# amp.net
KiCad netlist of a schematic drawn in EAGLE
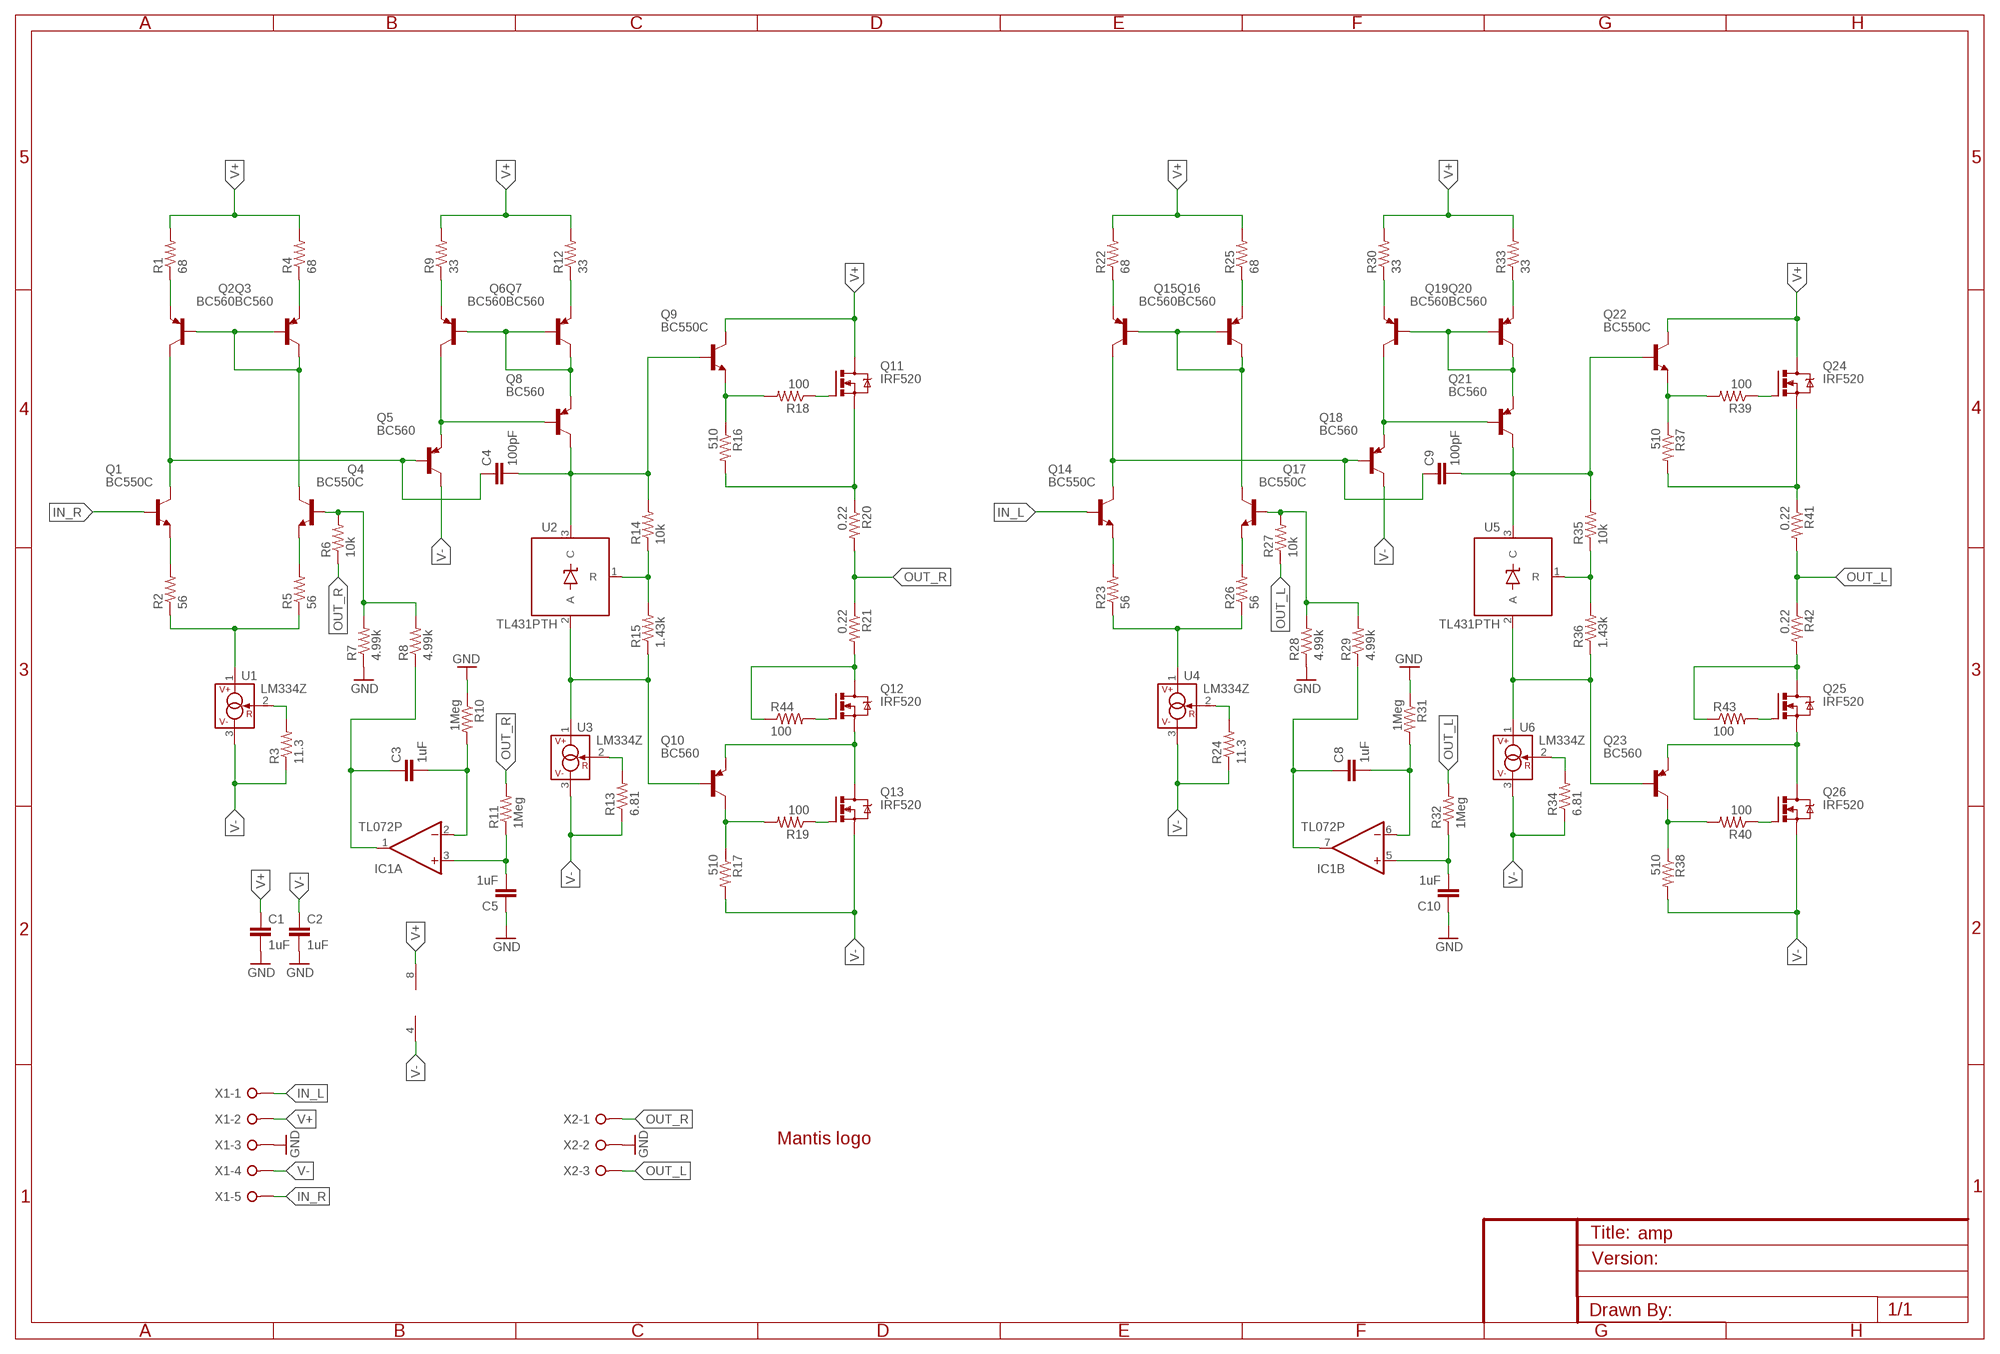
[diagram p0: schematic, sheet 1]

(export (version "E")
  (design (tool "Eeschema 10.0.6"))
  (components
    (comp (ref "C1")
      (value "1uF")
      (footprint "eagle-import:CAP-PTH-SMALL")
      (libsource (lib "eagle-import") (part "CAPPTH"))
    )
    (comp (ref "C2")
      (value "1uF")
      (footprint "eagle-import:CAP-PTH-SMALL")
      (libsource (lib "eagle-import") (part "CAPPTH"))
    )
    (comp (ref "C3")
      (value "1uF")
      (footprint "eagle-import:C5B5.5")
      (libsource (lib "eagle-import") (part "C5/5.5"))
    )
    (comp (ref "C4")
      (value "100pF")
      (footprint "eagle-import:C5B4.5")
      (libsource (lib "eagle-import") (part "C5/4.5"))
    )
    (comp (ref "C5")
      (value "1uF")
      (footprint "eagle-import:C5B5.5")
      (libsource (lib "eagle-import") (part "C5/5.5"))
    )
    (comp (ref "C8")
      (value "1uF")
      (footprint "eagle-import:C5B5.5")
      (libsource (lib "eagle-import") (part "C5/5.5"))
    )
    (comp (ref "C9")
      (value "100pF")
      (footprint "eagle-import:C5B4.5")
      (libsource (lib "eagle-import") (part "C5/4.5"))
    )
    (comp (ref "C10")
      (value "1uF")
      (footprint "eagle-import:C5B5.5")
      (libsource (lib "eagle-import") (part "C5/5.5"))
    )
    (comp (ref "IC1")
      (value "TL072P")
      (footprint "eagle-import:DIL08")
      (libsource (lib "eagle-import") (part "TL072P"))
    )
    (comp (ref "LOGO1")
      (value "LOGO-MANTIS")
      (footprint "eagle-import:LOGO-MANTIS")
      (libsource (lib "eagle-import") (part "LOGO-MANTIS"))
    )
    (comp (ref "Q1")
      (value "BC550C")
      (footprint "eagle-import:TO92-EBC")
      (libsource (lib "eagle-import") (part "BC550C"))
    )
    (comp (ref "Q2")
      (value "BC560")
      (footprint "eagle-import:TO92-EBC")
      (libsource (lib "eagle-import") (part "BC560"))
    )
    (comp (ref "Q3")
      (value "BC560")
      (footprint "eagle-import:TO92-EBC")
      (libsource (lib "eagle-import") (part "BC560"))
    )
    (comp (ref "Q4")
      (value "BC550C")
      (footprint "eagle-import:TO92-EBC")
      (libsource (lib "eagle-import") (part "BC550C"))
    )
    (comp (ref "Q5")
      (value "BC560")
      (footprint "eagle-import:TO92-EBC")
      (libsource (lib "eagle-import") (part "BC560"))
    )
    (comp (ref "Q6")
      (value "BC560")
      (footprint "eagle-import:TO92-EBC")
      (libsource (lib "eagle-import") (part "BC560"))
    )
    (comp (ref "Q7")
      (value "BC560")
      (footprint "eagle-import:TO92-EBC")
      (libsource (lib "eagle-import") (part "BC560"))
    )
    (comp (ref "Q8")
      (value "BC560")
      (footprint "eagle-import:TO92-EBC")
      (libsource (lib "eagle-import") (part "BC560"))
    )
    (comp (ref "Q9")
      (value "BC550C")
      (footprint "eagle-import:TO92-EBC")
      (libsource (lib "eagle-import") (part "BC550C"))
    )
    (comp (ref "Q10")
      (value "BC560")
      (footprint "eagle-import:TO92-EBC")
      (libsource (lib "eagle-import") (part "BC560"))
    )
    (comp (ref "Q11")
      (value "IRF520")
      (footprint "eagle-import:TO220BV")
      (libsource (lib "eagle-import") (part "IRF520"))
    )
    (comp (ref "Q12")
      (value "IRF520")
      (footprint "eagle-import:TO220BV")
      (libsource (lib "eagle-import") (part "IRF520"))
    )
    (comp (ref "Q13")
      (value "IRF520")
      (footprint "eagle-import:TO220BV")
      (libsource (lib "eagle-import") (part "IRF520"))
    )
    (comp (ref "Q14")
      (value "BC550C")
      (footprint "eagle-import:TO92-EBC")
      (libsource (lib "eagle-import") (part "BC550C"))
    )
    (comp (ref "Q15")
      (value "BC560")
      (footprint "eagle-import:TO92-EBC")
      (libsource (lib "eagle-import") (part "BC560"))
    )
    (comp (ref "Q16")
      (value "BC560")
      (footprint "eagle-import:TO92-EBC")
      (libsource (lib "eagle-import") (part "BC560"))
    )
    (comp (ref "Q17")
      (value "BC550C")
      (footprint "eagle-import:TO92-EBC")
      (libsource (lib "eagle-import") (part "BC550C"))
    )
    (comp (ref "Q18")
      (value "BC560")
      (footprint "eagle-import:TO92-EBC")
      (libsource (lib "eagle-import") (part "BC560"))
    )
    (comp (ref "Q19")
      (value "BC560")
      (footprint "eagle-import:TO92-EBC")
      (libsource (lib "eagle-import") (part "BC560"))
    )
    (comp (ref "Q20")
      (value "BC560")
      (footprint "eagle-import:TO92-EBC")
      (libsource (lib "eagle-import") (part "BC560"))
    )
    (comp (ref "Q21")
      (value "BC560")
      (footprint "eagle-import:TO92-EBC")
      (libsource (lib "eagle-import") (part "BC560"))
    )
    (comp (ref "Q22")
      (value "BC550C")
      (footprint "eagle-import:TO92-EBC")
      (libsource (lib "eagle-import") (part "BC550C"))
    )
    (comp (ref "Q23")
      (value "BC560")
      (footprint "eagle-import:TO92-EBC")
      (libsource (lib "eagle-import") (part "BC560"))
    )
    (comp (ref "Q24")
      (value "IRF520")
      (footprint "eagle-import:TO220BV")
      (libsource (lib "eagle-import") (part "IRF520"))
    )
    (comp (ref "Q25")
      (value "IRF520")
      (footprint "eagle-import:TO220BV")
      (libsource (lib "eagle-import") (part "IRF520"))
    )
    (comp (ref "Q26")
      (value "IRF520")
      (footprint "eagle-import:TO220BV")
      (libsource (lib "eagle-import") (part "IRF520"))
    )
    (comp (ref "R1")
      (value "68")
      (footprint "eagle-import:AXIAL-0.4")
      (libsource (lib "eagle-import") (part "RESISTORPTH-1/4W"))
    )
    (comp (ref "R2")
      (value "56")
      (footprint "eagle-import:AXIAL-0.4")
      (libsource (lib "eagle-import") (part "RESISTORPTH-1/4W"))
    )
    (comp (ref "R3")
      (value "11.3")
      (footprint "eagle-import:AXIAL-0.4")
      (libsource (lib "eagle-import") (part "RESISTORPTH-1/4W"))
    )
    (comp (ref "R4")
      (value "68")
      (footprint "eagle-import:AXIAL-0.4")
      (libsource (lib "eagle-import") (part "RESISTORPTH-1/4W"))
    )
    (comp (ref "R5")
      (value "56")
      (footprint "eagle-import:AXIAL-0.4")
      (libsource (lib "eagle-import") (part "RESISTORPTH-1/4W"))
    )
    (comp (ref "R6")
      (value "10k")
      (footprint "eagle-import:AXIAL-0.4")
      (libsource (lib "eagle-import") (part "RESISTORPTH-1/4W"))
    )
    (comp (ref "R7")
      (value "4.99k")
      (footprint "eagle-import:AXIAL-0.4")
      (libsource (lib "eagle-import") (part "RESISTORPTH-1/4W"))
    )
    (comp (ref "R8")
      (value "4.99k")
      (footprint "eagle-import:AXIAL-0.4")
      (libsource (lib "eagle-import") (part "RESISTORPTH-1/4W"))
    )
    (comp (ref "R9")
      (value "33")
      (footprint "eagle-import:AXIAL-0.4")
      (libsource (lib "eagle-import") (part "RESISTORPTH-1/4W"))
    )
    (comp (ref "R10")
      (value "1Meg")
      (footprint "eagle-import:AXIAL-0.4")
      (libsource (lib "eagle-import") (part "RESISTORPTH-1/4W"))
    )
    (comp (ref "R11")
      (value "1Meg")
      (footprint "eagle-import:AXIAL-0.4")
      (libsource (lib "eagle-import") (part "RESISTORPTH-1/4W"))
    )
    (comp (ref "R12")
      (value "33")
      (footprint "eagle-import:AXIAL-0.4")
      (libsource (lib "eagle-import") (part "RESISTORPTH-1/4W"))
    )
    (comp (ref "R13")
      (value "6.81")
      (footprint "eagle-import:AXIAL-0.4")
      (libsource (lib "eagle-import") (part "RESISTORPTH-1/4W"))
    )
    (comp (ref "R14")
      (value "10k")
      (footprint "eagle-import:AXIAL-0.4")
      (libsource (lib "eagle-import") (part "RESISTORPTH-1/4W"))
    )
    (comp (ref "R15")
      (value "1.43k")
      (footprint "eagle-import:AXIAL-0.4")
      (libsource (lib "eagle-import") (part "RESISTORPTH-1/4W"))
    )
    (comp (ref "R16")
      (value "510")
      (footprint "eagle-import:AXIAL-0.4")
      (libsource (lib "eagle-import") (part "RESISTORPTH-1/4W"))
    )
    (comp (ref "R17")
      (value "510")
      (footprint "eagle-import:AXIAL-0.4")
      (libsource (lib "eagle-import") (part "RESISTORPTH-1/4W"))
    )
    (comp (ref "R18")
      (value "100")
      (footprint "eagle-import:AXIAL-0.4")
      (libsource (lib "eagle-import") (part "RESISTORPTH-1/4W"))
    )
    (comp (ref "R19")
      (value "100")
      (footprint "eagle-import:AXIAL-0.4")
      (libsource (lib "eagle-import") (part "RESISTORPTH-1/4W"))
    )
    (comp (ref "R20")
      (value "0.22")
      (footprint "eagle-import:AXIAL-0.4")
      (libsource (lib "eagle-import") (part "RESISTORPTH-1/4W"))
    )
    (comp (ref "R21")
      (value "0.22")
      (footprint "eagle-import:AXIAL-0.4")
      (libsource (lib "eagle-import") (part "RESISTORPTH-1/4W"))
    )
    (comp (ref "R22")
      (value "68")
      (footprint "eagle-import:AXIAL-0.4")
      (libsource (lib "eagle-import") (part "RESISTORPTH-1/4W"))
    )
    (comp (ref "R23")
      (value "56")
      (footprint "eagle-import:AXIAL-0.4")
      (libsource (lib "eagle-import") (part "RESISTORPTH-1/4W"))
    )
    (comp (ref "R24")
      (value "11.3")
      (footprint "eagle-import:AXIAL-0.4")
      (libsource (lib "eagle-import") (part "RESISTORPTH-1/4W"))
    )
    (comp (ref "R25")
      (value "68")
      (footprint "eagle-import:AXIAL-0.4")
      (libsource (lib "eagle-import") (part "RESISTORPTH-1/4W"))
    )
    (comp (ref "R26")
      (value "56")
      (footprint "eagle-import:AXIAL-0.4")
      (libsource (lib "eagle-import") (part "RESISTORPTH-1/4W"))
    )
    (comp (ref "R27")
      (value "10k")
      (footprint "eagle-import:AXIAL-0.4")
      (libsource (lib "eagle-import") (part "RESISTORPTH-1/4W"))
    )
    (comp (ref "R28")
      (value "4.99k")
      (footprint "eagle-import:AXIAL-0.4")
      (libsource (lib "eagle-import") (part "RESISTORPTH-1/4W"))
    )
    (comp (ref "R29")
      (value "4.99k")
      (footprint "eagle-import:AXIAL-0.4")
      (libsource (lib "eagle-import") (part "RESISTORPTH-1/4W"))
    )
    (comp (ref "R30")
      (value "33")
      (footprint "eagle-import:AXIAL-0.4")
      (libsource (lib "eagle-import") (part "RESISTORPTH-1/4W"))
    )
    (comp (ref "R31")
      (value "1Meg")
      (footprint "eagle-import:AXIAL-0.4")
      (libsource (lib "eagle-import") (part "RESISTORPTH-1/4W"))
    )
    (comp (ref "R32")
      (value "1Meg")
      (footprint "eagle-import:AXIAL-0.4")
      (libsource (lib "eagle-import") (part "RESISTORPTH-1/4W"))
    )
    (comp (ref "R33")
      (value "33")
      (footprint "eagle-import:AXIAL-0.4")
      (libsource (lib "eagle-import") (part "RESISTORPTH-1/4W"))
    )
    (comp (ref "R34")
      (value "6.81")
      (footprint "eagle-import:AXIAL-0.4")
      (libsource (lib "eagle-import") (part "RESISTORPTH-1/4W"))
    )
    (comp (ref "R35")
      (value "10k")
      (footprint "eagle-import:AXIAL-0.4")
      (libsource (lib "eagle-import") (part "RESISTORPTH-1/4W"))
    )
    (comp (ref "R36")
      (value "1.43k")
      (footprint "eagle-import:AXIAL-0.4")
      (libsource (lib "eagle-import") (part "RESISTORPTH-1/4W"))
    )
    (comp (ref "R37")
      (value "510")
      (footprint "eagle-import:AXIAL-0.4")
      (libsource (lib "eagle-import") (part "RESISTORPTH-1/4W"))
    )
    (comp (ref "R38")
      (value "510")
      (footprint "eagle-import:AXIAL-0.4")
      (libsource (lib "eagle-import") (part "RESISTORPTH-1/4W"))
    )
    (comp (ref "R39")
      (value "100")
      (footprint "eagle-import:AXIAL-0.4")
      (libsource (lib "eagle-import") (part "RESISTORPTH-1/4W"))
    )
    (comp (ref "R40")
      (value "100")
      (footprint "eagle-import:AXIAL-0.4")
      (libsource (lib "eagle-import") (part "RESISTORPTH-1/4W"))
    )
    (comp (ref "R41")
      (value "0.22")
      (footprint "eagle-import:AXIAL-0.4")
      (libsource (lib "eagle-import") (part "RESISTORPTH-1/4W"))
    )
    (comp (ref "R42")
      (value "0.22")
      (footprint "eagle-import:AXIAL-0.4")
      (libsource (lib "eagle-import") (part "RESISTORPTH-1/4W"))
    )
    (comp (ref "R43")
      (value "100")
      (footprint "eagle-import:AXIAL-0.4")
      (libsource (lib "eagle-import") (part "RESISTORPTH-1/4W"))
    )
    (comp (ref "R44")
      (value "100")
      (footprint "eagle-import:AXIAL-0.4")
      (libsource (lib "eagle-import") (part "RESISTORPTH-1/4W"))
    )
    (comp (ref "U1")
      (value "LM334Z")
      (footprint "eagle-import:TO-92")
      (libsource (lib "eagle-import") (part "LM334Z"))
    )
    (comp (ref "U2")
      (value "TL431PTH")
      (footprint "eagle-import:TO-92")
      (libsource (lib "eagle-import") (part "TL431PTH"))
    )
    (comp (ref "U3")
      (value "LM334Z")
      (footprint "eagle-import:TO-92")
      (libsource (lib "eagle-import") (part "LM334Z"))
    )
    (comp (ref "U4")
      (value "LM334Z")
      (footprint "eagle-import:TO-92")
      (libsource (lib "eagle-import") (part "LM334Z"))
    )
    (comp (ref "U5")
      (value "TL431PTH")
      (footprint "eagle-import:TO-92")
      (libsource (lib "eagle-import") (part "TL431PTH"))
    )
    (comp (ref "U6")
      (value "LM334Z")
      (footprint "eagle-import:TO-92")
      (libsource (lib "eagle-import") (part "LM334Z"))
    )
    (comp (ref "X1")
      (value "W237-05P")
      (footprint "eagle-import:W237-5P")
      (libsource (lib "eagle-import") (part "W237-05P"))
    )
    (comp (ref "X2")
      (value "W237-3E")
      (footprint "eagle-import:W237-3E")
      (libsource (lib "eagle-import") (part "W237-3E"))
    )
  )
  (nets
    (net (code "1") (name "GND") (class "Default")
      (node (ref "C1") (pin "2") (pinfunction "2_2") (pintype "passive"))
      (node (ref "C10") (pin "1") (pinfunction "1_1") (pintype "passive"))
      (node (ref "C2") (pin "2") (pinfunction "2_2") (pintype "passive"))
      (node (ref "C5") (pin "1") (pinfunction "1_1") (pintype "passive"))
      (node (ref "R10") (pin "P$1") (pinfunction "1_P$1") (pintype "passive"))
      (node (ref "R28") (pin "P$1") (pinfunction "1_P$1") (pintype "passive"))
      (node (ref "R31") (pin "P$1") (pinfunction "1_P$1") (pintype "passive"))
      (node (ref "R7") (pin "P$1") (pinfunction "1_P$1") (pintype "passive"))
      (node (ref "X1") (pin "3") (pinfunction "KL_3") (pintype "passive"))
      (node (ref "X2") (pin "2") (pinfunction "KL_2") (pintype "passive"))
    )
    (net (code "2") (name "IN_L") (class "Default")
      (node (ref "Q14") (pin "B") (pinfunction "B_B") (pintype "passive"))
      (node (ref "X1") (pin "1") (pinfunction "KL_1") (pintype "passive"))
    )
    (net (code "3") (name "IN_R") (class "Default")
      (node (ref "Q1") (pin "B") (pinfunction "B_B") (pintype "passive"))
      (node (ref "X1") (pin "5") (pinfunction "KL_5") (pintype "passive"))
    )
    (net (code "4") (name "Net-(C4-Pad1)") (class "Default")
      (node (ref "C4") (pin "1") (pinfunction "1_1") (pintype "passive"))
      (node (ref "Q1") (pin "C") (pinfunction "C_C") (pintype "passive"))
      (node (ref "Q2") (pin "C") (pinfunction "C_C") (pintype "passive"))
      (node (ref "Q5") (pin "B") (pinfunction "B_B") (pintype "passive"))
    )
    (net (code "5") (name "Net-(C9-Pad1)") (class "Default")
      (node (ref "C9") (pin "1") (pinfunction "1_1") (pintype "passive"))
      (node (ref "Q14") (pin "C") (pinfunction "C_C") (pintype "passive"))
      (node (ref "Q15") (pin "C") (pinfunction "C_C") (pintype "passive"))
      (node (ref "Q18") (pin "B") (pinfunction "B_B") (pintype "passive"))
    )
    (net (code "6") (name "Net-(IC1A-+IN)") (class "Default")
      (node (ref "C5") (pin "2") (pinfunction "2_2") (pintype "passive"))
      (node (ref "IC1") (pin "3") (pinfunction "+IN_3") (pintype "input"))
      (node (ref "R11") (pin "P$1") (pinfunction "1_P$1") (pintype "passive"))
    )
    (net (code "7") (name "Net-(IC1A--IN)") (class "Default")
      (node (ref "C3") (pin "2") (pinfunction "2_2") (pintype "passive"))
      (node (ref "IC1") (pin "2") (pinfunction "-IN_2") (pintype "input"))
      (node (ref "R10") (pin "P$2") (pinfunction "2_P$2") (pintype "passive"))
    )
    (net (code "8") (name "Net-(IC1A-OUT)") (class "Default")
      (node (ref "C3") (pin "1") (pinfunction "1_1") (pintype "passive"))
      (node (ref "IC1") (pin "1") (pinfunction "OUT_1") (pintype "output"))
      (node (ref "R8") (pin "P$1") (pinfunction "1_P$1") (pintype "passive"))
    )
    (net (code "9") (name "Net-(IC1B-+IN)") (class "Default")
      (node (ref "C10") (pin "2") (pinfunction "2_2") (pintype "passive"))
      (node (ref "IC1") (pin "5") (pinfunction "+IN_5") (pintype "input"))
      (node (ref "R32") (pin "P$1") (pinfunction "1_P$1") (pintype "passive"))
    )
    (net (code "10") (name "Net-(IC1B--IN)") (class "Default")
      (node (ref "C8") (pin "2") (pinfunction "2_2") (pintype "passive"))
      (node (ref "IC1") (pin "6") (pinfunction "-IN_6") (pintype "input"))
      (node (ref "R31") (pin "P$2") (pinfunction "2_P$2") (pintype "passive"))
    )
    (net (code "11") (name "Net-(IC1B-OUT)") (class "Default")
      (node (ref "C8") (pin "1") (pinfunction "1_1") (pintype "passive"))
      (node (ref "IC1") (pin "7") (pinfunction "OUT_7") (pintype "output"))
      (node (ref "R29") (pin "P$1") (pinfunction "1_P$1") (pintype "passive"))
    )
    (net (code "12") (name "Net-(Q2-PadB)") (class "Default")
      (node (ref "Q2") (pin "B") (pinfunction "B_B") (pintype "passive"))
      (node (ref "Q3") (pin "B") (pinfunction "B_B") (pintype "passive"))
      (node (ref "Q3") (pin "C") (pinfunction "C_C") (pintype "passive"))
      (node (ref "Q4") (pin "C") (pinfunction "C_C") (pintype "passive"))
    )
    (net (code "13") (name "Net-(Q5-PadE)") (class "Default")
      (node (ref "Q5") (pin "E") (pinfunction "E_E") (pintype "passive"))
      (node (ref "Q6") (pin "C") (pinfunction "C_C") (pintype "passive"))
      (node (ref "Q8") (pin "B") (pinfunction "B_B") (pintype "passive"))
    )
    (net (code "14") (name "Net-(Q6-PadB)") (class "Default")
      (node (ref "Q6") (pin "B") (pinfunction "B_B") (pintype "passive"))
      (node (ref "Q7") (pin "B") (pinfunction "B_B") (pintype "passive"))
      (node (ref "Q7") (pin "C") (pinfunction "C_C") (pintype "passive"))
      (node (ref "Q8") (pin "E") (pinfunction "E_E") (pintype "passive"))
    )
    (net (code "15") (name "Net-(Q10-PadE)") (class "Default")
      (node (ref "Q10") (pin "E") (pinfunction "E_E") (pintype "passive"))
      (node (ref "Q12") (pin "S") (pinfunction "S_S") (pintype "passive"))
      (node (ref "Q13") (pin "D") (pinfunction "D_D") (pintype "passive"))
    )
    (net (code "16") (name "Net-(Q15-PadB)") (class "Default")
      (node (ref "Q15") (pin "B") (pinfunction "B_B") (pintype "passive"))
      (node (ref "Q16") (pin "B") (pinfunction "B_B") (pintype "passive"))
      (node (ref "Q16") (pin "C") (pinfunction "C_C") (pintype "passive"))
      (node (ref "Q17") (pin "C") (pinfunction "C_C") (pintype "passive"))
    )
    (net (code "17") (name "Net-(Q18-PadE)") (class "Default")
      (node (ref "Q18") (pin "E") (pinfunction "E_E") (pintype "passive"))
      (node (ref "Q19") (pin "C") (pinfunction "C_C") (pintype "passive"))
      (node (ref "Q21") (pin "B") (pinfunction "B_B") (pintype "passive"))
    )
    (net (code "18") (name "Net-(Q19-PadB)") (class "Default")
      (node (ref "Q19") (pin "B") (pinfunction "B_B") (pintype "passive"))
      (node (ref "Q20") (pin "B") (pinfunction "B_B") (pintype "passive"))
      (node (ref "Q20") (pin "C") (pinfunction "C_C") (pintype "passive"))
      (node (ref "Q21") (pin "E") (pinfunction "E_E") (pintype "passive"))
    )
    (net (code "19") (name "Net-(Q23-PadE)") (class "Default")
      (node (ref "Q23") (pin "E") (pinfunction "E_E") (pintype "passive"))
      (node (ref "Q25") (pin "S") (pinfunction "S_S") (pintype "passive"))
      (node (ref "Q26") (pin "D") (pinfunction "D_D") (pintype "passive"))
    )
    (net (code "20") (name "Net-(R1-1)") (class "Default")
      (node (ref "Q2") (pin "E") (pinfunction "E_E") (pintype "passive"))
      (node (ref "R1") (pin "P$1") (pinfunction "1_P$1") (pintype "passive"))
    )
    (net (code "21") (name "Net-(R2-1)") (class "Default")
      (node (ref "R2") (pin "P$1") (pinfunction "1_P$1") (pintype "passive"))
      (node (ref "R5") (pin "P$1") (pinfunction "1_P$1") (pintype "passive"))
      (node (ref "U1") (pin "1") (pinfunction "V+_1") (pintype "passive"))
    )
    (net (code "22") (name "Net-(R2-2)") (class "Default")
      (node (ref "Q1") (pin "E") (pinfunction "E_E") (pintype "passive"))
      (node (ref "R2") (pin "P$2") (pinfunction "2_P$2") (pintype "passive"))
    )
    (net (code "23") (name "Net-(R3-2)") (class "Default")
      (node (ref "R3") (pin "P$2") (pinfunction "2_P$2") (pintype "passive"))
      (node (ref "U1") (pin "2") (pinfunction "R_2") (pintype "passive"))
    )
    (net (code "24") (name "Net-(R4-1)") (class "Default")
      (node (ref "Q3") (pin "E") (pinfunction "E_E") (pintype "passive"))
      (node (ref "R4") (pin "P$1") (pinfunction "1_P$1") (pintype "passive"))
    )
    (net (code "25") (name "Net-(R5-2)") (class "Default")
      (node (ref "Q4") (pin "E") (pinfunction "E_E") (pintype "passive"))
      (node (ref "R5") (pin "P$2") (pinfunction "2_P$2") (pintype "passive"))
    )
    (net (code "26") (name "Net-(R6-2)") (class "Default")
      (node (ref "Q4") (pin "B") (pinfunction "B_B") (pintype "passive"))
      (node (ref "R6") (pin "P$2") (pinfunction "2_P$2") (pintype "passive"))
      (node (ref "R7") (pin "P$2") (pinfunction "2_P$2") (pintype "passive"))
      (node (ref "R8") (pin "P$2") (pinfunction "2_P$2") (pintype "passive"))
    )
    (net (code "27") (name "Net-(R9-1)") (class "Default")
      (node (ref "Q6") (pin "E") (pinfunction "E_E") (pintype "passive"))
      (node (ref "R9") (pin "P$1") (pinfunction "1_P$1") (pintype "passive"))
    )
    (net (code "28") (name "Net-(R12-1)") (class "Default")
      (node (ref "Q7") (pin "E") (pinfunction "E_E") (pintype "passive"))
      (node (ref "R12") (pin "P$1") (pinfunction "1_P$1") (pintype "passive"))
    )
    (net (code "29") (name "Net-(R13-2)") (class "Default")
      (node (ref "R13") (pin "P$2") (pinfunction "2_P$2") (pintype "passive"))
      (node (ref "U3") (pin "2") (pinfunction "R_2") (pintype "passive"))
    )
    (net (code "30") (name "Net-(R14-1)") (class "Default")
      (node (ref "R14") (pin "P$1") (pinfunction "1_P$1") (pintype "passive"))
      (node (ref "R15") (pin "P$2") (pinfunction "2_P$2") (pintype "passive"))
      (node (ref "U2") (pin "1") (pinfunction "R_1") (pintype "bidirectional"))
    )
    (net (code "31") (name "Net-(R14-2)") (class "Default")
      (node (ref "C4") (pin "2") (pinfunction "2_2") (pintype "passive"))
      (node (ref "Q8") (pin "C") (pinfunction "C_C") (pintype "passive"))
      (node (ref "Q9") (pin "B") (pinfunction "B_B") (pintype "passive"))
      (node (ref "R14") (pin "P$2") (pinfunction "2_P$2") (pintype "passive"))
      (node (ref "U2") (pin "3") (pinfunction "C_3") (pintype "bidirectional"))
    )
    (net (code "32") (name "Net-(R15-1)") (class "Default")
      (node (ref "Q10") (pin "B") (pinfunction "B_B") (pintype "passive"))
      (node (ref "R15") (pin "P$1") (pinfunction "1_P$1") (pintype "passive"))
      (node (ref "U2") (pin "2") (pinfunction "A_2") (pintype "bidirectional"))
      (node (ref "U3") (pin "1") (pinfunction "V+_1") (pintype "passive"))
    )
    (net (code "33") (name "Net-(R16-1)") (class "Default")
      (node (ref "Q9") (pin "E") (pinfunction "E_E") (pintype "passive"))
      (node (ref "R16") (pin "P$1") (pinfunction "1_P$1") (pintype "passive"))
      (node (ref "R18") (pin "P$2") (pinfunction "2_P$2") (pintype "passive"))
    )
    (net (code "34") (name "Net-(R16-2)") (class "Default")
      (node (ref "Q11") (pin "S") (pinfunction "S_S") (pintype "passive"))
      (node (ref "R16") (pin "P$2") (pinfunction "2_P$2") (pintype "passive"))
      (node (ref "R20") (pin "P$1") (pinfunction "1_P$1") (pintype "passive"))
    )
    (net (code "35") (name "Net-(R17-1)") (class "Default")
      (node (ref "Q10") (pin "C") (pinfunction "C_C") (pintype "passive"))
      (node (ref "R17") (pin "P$1") (pinfunction "1_P$1") (pintype "passive"))
      (node (ref "R19") (pin "P$2") (pinfunction "2_P$2") (pintype "passive"))
    )
    (net (code "36") (name "Net-(R18-1)") (class "Default")
      (node (ref "Q11") (pin "G") (pinfunction "G_G") (pintype "passive"))
      (node (ref "R18") (pin "P$1") (pinfunction "1_P$1") (pintype "passive"))
    )
    (net (code "37") (name "Net-(R19-1)") (class "Default")
      (node (ref "Q13") (pin "G") (pinfunction "G_G") (pintype "passive"))
      (node (ref "R19") (pin "P$1") (pinfunction "1_P$1") (pintype "passive"))
    )
    (net (code "38") (name "Net-(R21-2)") (class "Default")
      (node (ref "Q12") (pin "D") (pinfunction "D_D") (pintype "passive"))
      (node (ref "R21") (pin "P$2") (pinfunction "2_P$2") (pintype "passive"))
      (node (ref "R44") (pin "P$1") (pinfunction "1_P$1") (pintype "passive"))
    )
    (net (code "39") (name "Net-(R22-1)") (class "Default")
      (node (ref "Q15") (pin "E") (pinfunction "E_E") (pintype "passive"))
      (node (ref "R22") (pin "P$1") (pinfunction "1_P$1") (pintype "passive"))
    )
    (net (code "40") (name "Net-(R23-1)") (class "Default")
      (node (ref "R23") (pin "P$1") (pinfunction "1_P$1") (pintype "passive"))
      (node (ref "R26") (pin "P$1") (pinfunction "1_P$1") (pintype "passive"))
      (node (ref "U4") (pin "1") (pinfunction "V+_1") (pintype "passive"))
    )
    (net (code "41") (name "Net-(R23-2)") (class "Default")
      (node (ref "Q14") (pin "E") (pinfunction "E_E") (pintype "passive"))
      (node (ref "R23") (pin "P$2") (pinfunction "2_P$2") (pintype "passive"))
    )
    (net (code "42") (name "Net-(R24-2)") (class "Default")
      (node (ref "R24") (pin "P$2") (pinfunction "2_P$2") (pintype "passive"))
      (node (ref "U4") (pin "2") (pinfunction "R_2") (pintype "passive"))
    )
    (net (code "43") (name "Net-(R25-1)") (class "Default")
      (node (ref "Q16") (pin "E") (pinfunction "E_E") (pintype "passive"))
      (node (ref "R25") (pin "P$1") (pinfunction "1_P$1") (pintype "passive"))
    )
    (net (code "44") (name "Net-(R26-2)") (class "Default")
      (node (ref "Q17") (pin "E") (pinfunction "E_E") (pintype "passive"))
      (node (ref "R26") (pin "P$2") (pinfunction "2_P$2") (pintype "passive"))
    )
    (net (code "45") (name "Net-(R27-2)") (class "Default")
      (node (ref "Q17") (pin "B") (pinfunction "B_B") (pintype "passive"))
      (node (ref "R27") (pin "P$2") (pinfunction "2_P$2") (pintype "passive"))
      (node (ref "R28") (pin "P$2") (pinfunction "2_P$2") (pintype "passive"))
      (node (ref "R29") (pin "P$2") (pinfunction "2_P$2") (pintype "passive"))
    )
    (net (code "46") (name "Net-(R30-1)") (class "Default")
      (node (ref "Q19") (pin "E") (pinfunction "E_E") (pintype "passive"))
      (node (ref "R30") (pin "P$1") (pinfunction "1_P$1") (pintype "passive"))
    )
    (net (code "47") (name "Net-(R33-1)") (class "Default")
      (node (ref "Q20") (pin "E") (pinfunction "E_E") (pintype "passive"))
      (node (ref "R33") (pin "P$1") (pinfunction "1_P$1") (pintype "passive"))
    )
    (net (code "48") (name "Net-(R34-2)") (class "Default")
      (node (ref "R34") (pin "P$2") (pinfunction "2_P$2") (pintype "passive"))
      (node (ref "U6") (pin "2") (pinfunction "R_2") (pintype "passive"))
    )
    (net (code "49") (name "Net-(R35-1)") (class "Default")
      (node (ref "R35") (pin "P$1") (pinfunction "1_P$1") (pintype "passive"))
      (node (ref "R36") (pin "P$2") (pinfunction "2_P$2") (pintype "passive"))
      (node (ref "U5") (pin "1") (pinfunction "R_1") (pintype "bidirectional"))
    )
    (net (code "50") (name "Net-(R35-2)") (class "Default")
      (node (ref "C9") (pin "2") (pinfunction "2_2") (pintype "passive"))
      (node (ref "Q21") (pin "C") (pinfunction "C_C") (pintype "passive"))
      (node (ref "Q22") (pin "B") (pinfunction "B_B") (pintype "passive"))
      (node (ref "R35") (pin "P$2") (pinfunction "2_P$2") (pintype "passive"))
      (node (ref "U5") (pin "3") (pinfunction "C_3") (pintype "bidirectional"))
    )
    (net (code "51") (name "Net-(R36-1)") (class "Default")
      (node (ref "Q23") (pin "B") (pinfunction "B_B") (pintype "passive"))
      (node (ref "R36") (pin "P$1") (pinfunction "1_P$1") (pintype "passive"))
      (node (ref "U5") (pin "2") (pinfunction "A_2") (pintype "bidirectional"))
      (node (ref "U6") (pin "1") (pinfunction "V+_1") (pintype "passive"))
    )
    (net (code "52") (name "Net-(R37-1)") (class "Default")
      (node (ref "Q22") (pin "E") (pinfunction "E_E") (pintype "passive"))
      (node (ref "R37") (pin "P$1") (pinfunction "1_P$1") (pintype "passive"))
      (node (ref "R39") (pin "P$2") (pinfunction "2_P$2") (pintype "passive"))
    )
    (net (code "53") (name "Net-(R37-2)") (class "Default")
      (node (ref "Q24") (pin "S") (pinfunction "S_S") (pintype "passive"))
      (node (ref "R37") (pin "P$2") (pinfunction "2_P$2") (pintype "passive"))
      (node (ref "R41") (pin "P$1") (pinfunction "1_P$1") (pintype "passive"))
    )
    (net (code "54") (name "Net-(R38-1)") (class "Default")
      (node (ref "Q23") (pin "C") (pinfunction "C_C") (pintype "passive"))
      (node (ref "R38") (pin "P$1") (pinfunction "1_P$1") (pintype "passive"))
      (node (ref "R40") (pin "P$2") (pinfunction "2_P$2") (pintype "passive"))
    )
    (net (code "55") (name "Net-(R39-1)") (class "Default")
      (node (ref "Q24") (pin "G") (pinfunction "G_G") (pintype "passive"))
      (node (ref "R39") (pin "P$1") (pinfunction "1_P$1") (pintype "passive"))
    )
    (net (code "56") (name "Net-(R40-1)") (class "Default")
      (node (ref "Q26") (pin "G") (pinfunction "G_G") (pintype "passive"))
      (node (ref "R40") (pin "P$1") (pinfunction "1_P$1") (pintype "passive"))
    )
    (net (code "57") (name "Net-(R42-2)") (class "Default")
      (node (ref "Q25") (pin "D") (pinfunction "D_D") (pintype "passive"))
      (node (ref "R42") (pin "P$2") (pinfunction "2_P$2") (pintype "passive"))
      (node (ref "R43") (pin "P$1") (pinfunction "1_P$1") (pintype "passive"))
    )
    (net (code "58") (name "Net-(R43-2)") (class "Default")
      (node (ref "Q25") (pin "G") (pinfunction "G_G") (pintype "passive"))
      (node (ref "R43") (pin "P$2") (pinfunction "2_P$2") (pintype "passive"))
    )
    (net (code "59") (name "Net-(R44-2)") (class "Default")
      (node (ref "Q12") (pin "G") (pinfunction "G_G") (pintype "passive"))
      (node (ref "R44") (pin "P$2") (pinfunction "2_P$2") (pintype "passive"))
    )
    (net (code "60") (name "OUT_L") (class "Default")
      (node (ref "R27") (pin "P$1") (pinfunction "1_P$1") (pintype "passive"))
      (node (ref "R32") (pin "P$2") (pinfunction "2_P$2") (pintype "passive"))
      (node (ref "R41") (pin "P$2") (pinfunction "2_P$2") (pintype "passive"))
      (node (ref "R42") (pin "P$1") (pinfunction "1_P$1") (pintype "passive"))
      (node (ref "X2") (pin "3") (pinfunction "KL_3") (pintype "passive"))
    )
    (net (code "61") (name "OUT_R") (class "Default")
      (node (ref "R11") (pin "P$2") (pinfunction "2_P$2") (pintype "passive"))
      (node (ref "R20") (pin "P$2") (pinfunction "2_P$2") (pintype "passive"))
      (node (ref "R21") (pin "P$1") (pinfunction "1_P$1") (pintype "passive"))
      (node (ref "R6") (pin "P$1") (pinfunction "1_P$1") (pintype "passive"))
      (node (ref "X2") (pin "1") (pinfunction "KL_1") (pintype "passive"))
    )
    (net (code "62") (name "V+") (class "Default")
      (node (ref "C1") (pin "1") (pinfunction "1_1") (pintype "passive"))
      (node (ref "IC1") (pin "8") (pinfunction "V+_8") (pintype "power_in"))
      (node (ref "Q11") (pin "D") (pinfunction "D_D") (pintype "passive"))
      (node (ref "Q22") (pin "C") (pinfunction "C_C") (pintype "passive"))
      (node (ref "Q24") (pin "D") (pinfunction "D_D") (pintype "passive"))
      (node (ref "Q9") (pin "C") (pinfunction "C_C") (pintype "passive"))
      (node (ref "R1") (pin "P$2") (pinfunction "2_P$2") (pintype "passive"))
      (node (ref "R12") (pin "P$2") (pinfunction "2_P$2") (pintype "passive"))
      (node (ref "R22") (pin "P$2") (pinfunction "2_P$2") (pintype "passive"))
      (node (ref "R25") (pin "P$2") (pinfunction "2_P$2") (pintype "passive"))
      (node (ref "R30") (pin "P$2") (pinfunction "2_P$2") (pintype "passive"))
      (node (ref "R33") (pin "P$2") (pinfunction "2_P$2") (pintype "passive"))
      (node (ref "R4") (pin "P$2") (pinfunction "2_P$2") (pintype "passive"))
      (node (ref "R9") (pin "P$2") (pinfunction "2_P$2") (pintype "passive"))
      (node (ref "X1") (pin "2") (pinfunction "KL_2") (pintype "passive"))
    )
    (net (code "63") (name "V-") (class "Default")
      (node (ref "C2") (pin "1") (pinfunction "1_1") (pintype "passive"))
      (node (ref "IC1") (pin "4") (pinfunction "V-_4") (pintype "power_in"))
      (node (ref "Q13") (pin "S") (pinfunction "S_S") (pintype "passive"))
      (node (ref "Q18") (pin "C") (pinfunction "C_C") (pintype "passive"))
      (node (ref "Q26") (pin "S") (pinfunction "S_S") (pintype "passive"))
      (node (ref "Q5") (pin "C") (pinfunction "C_C") (pintype "passive"))
      (node (ref "R13") (pin "P$1") (pinfunction "1_P$1") (pintype "passive"))
      (node (ref "R17") (pin "P$2") (pinfunction "2_P$2") (pintype "passive"))
      (node (ref "R24") (pin "P$1") (pinfunction "1_P$1") (pintype "passive"))
      (node (ref "R3") (pin "P$1") (pinfunction "1_P$1") (pintype "passive"))
      (node (ref "R34") (pin "P$1") (pinfunction "1_P$1") (pintype "passive"))
      (node (ref "R38") (pin "P$2") (pinfunction "2_P$2") (pintype "passive"))
      (node (ref "U1") (pin "3") (pinfunction "V-_3") (pintype "passive"))
      (node (ref "U3") (pin "3") (pinfunction "V-_3") (pintype "passive"))
      (node (ref "U4") (pin "3") (pinfunction "V-_3") (pintype "passive"))
      (node (ref "U6") (pin "3") (pinfunction "V-_3") (pintype "passive"))
      (node (ref "X1") (pin "4") (pinfunction "KL_4") (pintype "passive"))
    )
  )
)
